# iobrd.net
KiCad netlist of a schematic drawn in Altium Designer
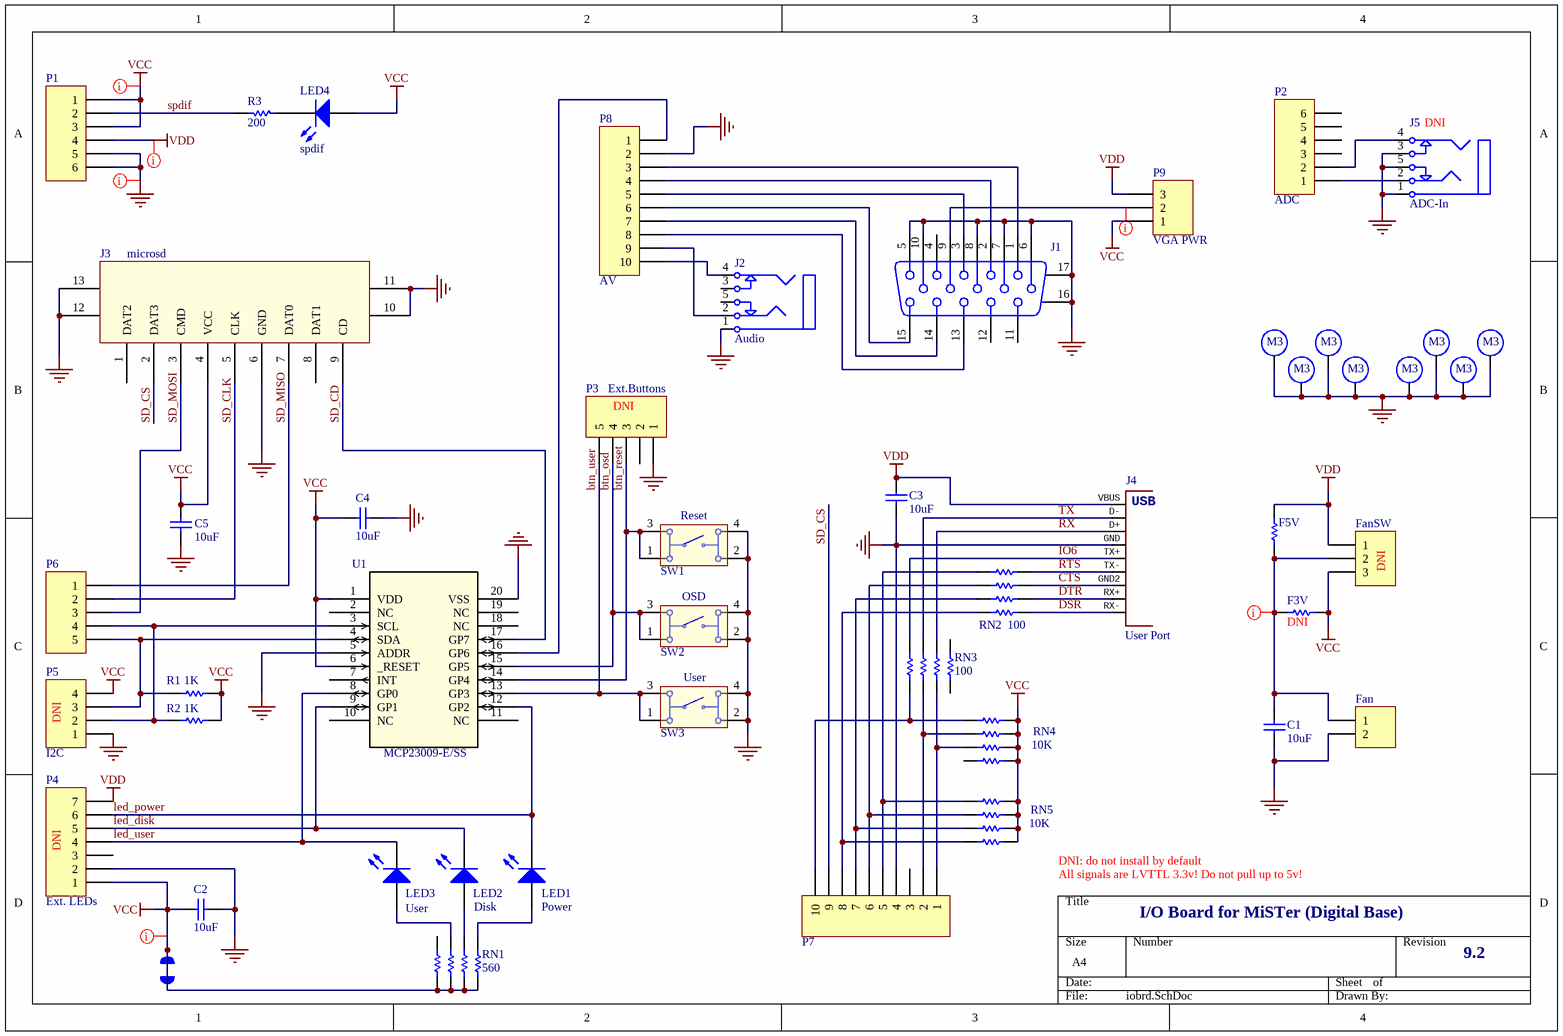
[diagram p0: iobrd.SchDoc]

(export (version "E")
  (design (tool "Eeschema 10.0.6"))
  (components
    (comp (ref "C1")
      (value "10uF")
      (footprint "C0805")
      (description "Ceramic Chip Capacitor - Standard")
      (fields (field (name "Comment") "C0805") (field (name "PUBLISHER") "Altium Limited"))
      (libsource (lib "lib") (part "C0805"))
    )
    (comp (ref "C2")
      (value "10uF")
      (footprint "C0805")
      (description "Ceramic Chip Capacitor - Standard")
      (fields (field (name "Comment") "C0805") (field (name "PUBLISHER") "Altium Limited"))
      (libsource (lib "lib") (part "C0805"))
    )
    (comp (ref "C3")
      (value "10uF")
      (footprint "C0805")
      (description "Ceramic Chip Capacitor - Standard")
      (fields (field (name "Comment") "C0805") (field (name "PUBLISHER") "Altium Limited"))
      (libsource (lib "lib") (part "C0805"))
    )
    (comp (ref "C4")
      (value "10uF")
      (footprint "C0805")
      (description "Ceramic Chip Capacitor - Standard")
      (fields (field (name "Comment") "C0805") (field (name "PUBLISHER") "Altium Limited"))
      (libsource (lib "lib") (part "C0805"))
    )
    (comp (ref "C5")
      (value "10uF")
      (footprint "C0805")
      (description "Ceramic Chip Capacitor - Standard")
      (fields (field (name "Comment") "C0805") (field (name "PUBLISHER") "Altium Limited"))
      (libsource (lib "lib") (part "C0805"))
    )
    (comp (ref "CUT1") (value "CUT") (libsource (lib "lib") (part "CUT")))
    (comp (ref "F3V")
      (value "0")
      (footprint "R0805 - DNI")
      (fields (field (name "PUBLISHER") "Altium Limited"))
      (libsource (lib "lib") (part "R0805"))
    )
    (comp (ref "F5V")
      (value "0")
      (footprint "R0805")
      (fields (field (name "PUBLISHER") "Altium Limited"))
      (libsource (lib "lib") (part "R0805"))
    )
    (comp (ref "Fan")
      (value "Header 2")
      (footprint "HDR1X2")
      (description "Header, 2-Pin")
      (fields (field (name "PUBLISHER") "Altium Limited"))
      (libsource (lib "Miscellaneous Connectors") (part "Header 2"))
    )
    (comp (ref "FanSW")
      (value "Header 3")
      (footprint "HDR1X3")
      (description "Header, 3-Pin")
      (fields (field (name "PUBLISHER") "Altium Limited"))
      (libsource (lib "Miscellaneous Connectors") (part "Header 3"))
    )
    (comp (ref "H1") (value "~") (footprint "M3") (libsource (lib "lib") (part "M3")))
    (comp (ref "H2") (value "~") (footprint "M3") (libsource (lib "lib") (part "M3")))
    (comp (ref "H3") (value "~") (footprint "M3") (libsource (lib "lib") (part "M3")))
    (comp (ref "H4") (value "~") (footprint "M3") (libsource (lib "lib") (part "M3")))
    (comp (ref "H5") (value "~") (footprint "M3") (libsource (lib "lib") (part "M3")))
    (comp (ref "H6") (value "~") (footprint "M3") (libsource (lib "lib") (part "M3")))
    (comp (ref "H7") (value "~") (footprint "M3") (libsource (lib "lib") (part "M3")))
    (comp (ref "H8") (value "~") (footprint "M3") (libsource (lib "lib") (part "M3")))
    (comp (ref "J1") (value "vga") (footprint "VGA") (libsource (lib "lib") (part "vga")))
    (comp (ref "J2") (value "Audio") (footprint "phonejack") (libsource (lib "lib") (part "phonejack")))
    (comp (ref "J3") (value "microsd") (footprint "microsd") (libsource (lib "lib") (part "microsd")))
    (comp (ref "J4")
      (value "User Port")
      (footprint "USB3-A-F-PTH")
      (fields (field (name "USB") "USB"))
      (libsource (lib "lib") (part "USBA30-PTH"))
    )
    (comp (ref "J5")
      (value "ADC-In")
      (footprint "phonejack - DNI")
      (libsource (lib "lib") (part "phonejack"))
    )
    (comp (ref "LED1")
      (value "Power")
      (footprint "LEDR")
      (description "THT LED round mono-color color lens, WL-TMRW, Super Red")
      (fields (field (name "PARTNUMBER") "151031SS04000"))
      (libsource (lib "WL-TMRC THT LED round mono-color color lens") (part "151031SS04000"))
    )
    (comp (ref "LED2")
      (value "Disk")
      (footprint "LEDG")
      (description "THT LED round mono-color color lens, WL-TMRW, Super Red")
      (fields (field (name "PARTNUMBER") "151031SS04000"))
      (libsource (lib "WL-TMRC THT LED round mono-color color lens") (part "151031SS04000"))
    )
    (comp (ref "LED3")
      (value "User")
      (footprint "LEDY")
      (description "THT LED round mono-color color lens, WL-TMRW, Super Red")
      (fields (field (name "PARTNUMBER") "151031SS04000"))
      (libsource (lib "WL-TMRC THT LED round mono-color color lens") (part "151031SS04000"))
    )
    (comp (ref "LED4")
      (value "spdif")
      (footprint "LEDR_angle")
      (description "THT LED round mono-color color lens, WL-TMRW, Super Red")
      (fields (field (name "PARTNUMBER") "151031SS04000"))
      (libsource (lib "WL-TMRC THT LED round mono-color color lens") (part "151031SS04000"))
    )
    (comp (ref "P1")
      (value "~")
      (footprint "HDR1X6")
      (description "Header, 6-Pin")
      (fields (field (name "PUBLISHER") "Altium Limited"))
      (libsource (lib "Miscellaneous Connectors") (part "Header 6"))
    )
    (comp (ref "P2")
      (value "ADC")
      (footprint "HDR1X6")
      (description "Header, 6-Pin")
      (fields (field (name "PUBLISHER") "Altium Limited"))
      (libsource (lib "") (part "Header 6_1"))
    )
    (comp (ref "P3")
      (value "Ext.Buttons")
      (footprint "HDR5")
      (description "Header, 5-Pin")
      (fields (field (name "PUBLISHER") "Altium Limited"))
      (libsource (lib "Miscellaneous Connectors") (part "Header 5"))
    )
    (comp (ref "P4")
      (value "Ext. LEDs")
      (footprint "HDR7")
      (description "Header, 7-Pin")
      (fields (field (name "PUBLISHER") "Altium Limited"))
      (libsource (lib "Miscellaneous Connectors") (part "Header 7"))
    )
    (comp (ref "P5")
      (value "I2C")
      (footprint "HDR1X4")
      (description "Header, 4-Pin")
      (fields (field (name "PUBLISHER") "Altium Limited"))
      (libsource (lib "Miscellaneous Connectors") (part "Header 4"))
    )
    (comp (ref "P6")
      (value "Header 5")
      (footprint "HDR1X5")
      (description "Header, 5-Pin")
      (fields (field (name "PUBLISHER") "Altium Limited"))
      (libsource (lib "") (part "Header 5_1"))
    )
    (comp (ref "P7")
      (value "Header 10")
      (footprint "HDR1X10")
      (description "Header, 10-Pin")
      (fields (field (name "PUBLISHER") "Altium Limited"))
      (libsource (lib "Miscellaneous Connectors") (part "Header 10"))
    )
    (comp (ref "P8")
      (value "AV")
      (footprint "HDR1X10")
      (description "Header, 10-Pin")
      (fields (field (name "PUBLISHER") "Altium Limited"))
      (libsource (lib "Miscellaneous Connectors") (part "Header 10"))
    )
    (comp (ref "P9")
      (value "VGA PWR")
      (footprint "HDR1X3")
      (description "Header, 3-Pin")
      (fields (field (name "PUBLISHER") "Altium Limited"))
      (libsource (lib "") (part "Header 3_1"))
    )
    (comp (ref "R1")
      (value "1K")
      (footprint "R0805")
      (fields (field (name "PUBLISHER") "Altium Limited"))
      (libsource (lib "lib") (part "R0805"))
    )
    (comp (ref "R2")
      (value "1K")
      (footprint "R0805")
      (fields (field (name "PUBLISHER") "Altium Limited"))
      (libsource (lib "lib") (part "R0805"))
    )
    (comp (ref "R3")
      (value "200")
      (footprint "R0805")
      (fields (field (name "PUBLISHER") "Altium Limited"))
      (libsource (lib "lib") (part "R0805"))
    )
    (comp (ref "RN1") (value "560") (footprint "RA1206") (libsource (lib "lib") (part "resistor_set")))
    (comp (ref "RN2") (value "100") (footprint "RA1206") (libsource (lib "lib") (part "resistor_set")))
    (comp (ref "RN3") (value "100") (footprint "RA1206") (libsource (lib "") (part "resistor_set_1")))
    (comp (ref "RN4") (value "10K") (footprint "RA1206") (libsource (lib "lib") (part "resistor_set")))
    (comp (ref "RN5") (value "10K") (footprint "RA1206") (libsource (lib "lib") (part "resistor_set")))
    (comp (ref "SW1")
      (value "Reset")
      (footprint "tact 12x12")
      (libsource (lib "Schlib1") (part "tact 12x12"))
    )
    (comp (ref "SW2") (value "OSD") (footprint "tact 12x12") (libsource (lib "Schlib1") (part "tact 12x12")))
    (comp (ref "SW3") (value "User") (footprint "tact 12x12") (libsource (lib "Schlib1") (part "tact 12x12")))
    (comp (ref "U1")
      (value "MCP23009-E/SS")
      (footprint "SSOP20_MC")
      (description "MCP23009")
      (fields (field (name "COPYRIGHT") "Copyright (C) 2018 Accelerated Designs. All rights reserved"))
      (libsource (lib "lib") (part "MCP23009-E/SS"))
    )
  )
  (nets
    (net (code "1") (name "/CTS") (class "Default")
      (node (ref "J4") (pin "GND2") (pinfunction "GND2_GND2") (pintype "passive"))
      (node (ref "RN2") (pin "5") (pinfunction "5_5") (pintype "passive"))
    )
    (net (code "2") (name "/DSR") (class "Default")
      (node (ref "J4") (pin "RX-") (pinfunction "RX-_RX-") (pintype "passive"))
      (node (ref "RN2") (pin "1") (pinfunction "1_1") (pintype "passive"))
    )
    (net (code "3") (name "/DTR") (class "Default")
      (node (ref "J4") (pin "RX+") (pinfunction "RX+_RX+") (pintype "passive"))
      (node (ref "RN2") (pin "3") (pinfunction "3_3") (pintype "passive"))
    )
    (net (code "4") (name "/IO6") (class "Default")
      (node (ref "J4") (pin "TX+") (pinfunction "TX+_TX+") (pintype "passive"))
      (node (ref "RN3") (pin "1") (pinfunction "1_1") (pintype "passive"))
    )
    (net (code "5") (name "/RTS") (class "Default")
      (node (ref "J4") (pin "TX-") (pinfunction "TX-_TX-") (pintype "passive"))
      (node (ref "RN2") (pin "7") (pinfunction "7_7") (pintype "passive"))
    )
    (net (code "6") (name "/RX") (class "Default")
      (node (ref "J4") (pin "D+") (pinfunction "D+_D+") (pintype "passive"))
      (node (ref "RN3") (pin "5") (pinfunction "5_5") (pintype "passive"))
    )
    (net (code "7") (name "/SD_CD") (class "Default")
      (node (ref "J3") (pin "9") (pinfunction "CD_9") (pintype "passive"))
      (node (ref "U1") (pin "17") (pinfunction "GP7_17") (pintype "passive"))
    )
    (net (code "8") (name "/SD_CLK") (class "Default")
      (node (ref "J3") (pin "5") (pinfunction "CLK_5") (pintype "passive"))
      (node (ref "P6") (pin "2") (pinfunction "2_2") (pintype "passive"))
    )
    (net (code "9") (name "/SD_CS") (class "Default")
      (node (ref "J3") (pin "2") (pinfunction "DAT3_2") (pintype "passive"))
      (node (ref "P7") (pin "9") (pinfunction "9_9") (pintype "passive"))
    )
    (net (code "10") (name "/SD_MISO") (class "Default")
      (node (ref "J3") (pin "7") (pinfunction "DAT0_7") (pintype "passive"))
      (node (ref "P6") (pin "1") (pinfunction "1_1") (pintype "passive"))
    )
    (net (code "11") (name "/SD_MOSI") (class "Default")
      (node (ref "J3") (pin "3") (pinfunction "CMD_3") (pintype "passive"))
      (node (ref "P6") (pin "3") (pinfunction "3_3") (pintype "passive"))
    )
    (net (code "12") (name "/TX") (class "Default")
      (node (ref "J4") (pin "D-") (pinfunction "D-_D-") (pintype "passive"))
      (node (ref "RN3") (pin "3") (pinfunction "3_3") (pintype "passive"))
    )
    (net (code "13") (name "/btn_osd") (class "Default")
      (node (ref "P3") (pin "4") (pinfunction "4_4") (pintype "passive"))
      (node (ref "SW2") (pin "1") (pinfunction "1_1") (pintype "passive"))
      (node (ref "SW2") (pin "3") (pinfunction "3_3") (pintype "passive"))
      (node (ref "U1") (pin "15") (pinfunction "GP5_15") (pintype "passive"))
    )
    (net (code "14") (name "/btn_reset") (class "Default")
      (node (ref "P3") (pin "3") (pinfunction "3_3") (pintype "passive"))
      (node (ref "SW1") (pin "1") (pinfunction "1_1") (pintype "passive"))
      (node (ref "SW1") (pin "3") (pinfunction "3_3") (pintype "passive"))
      (node (ref "U1") (pin "14") (pinfunction "GP4_14") (pintype "passive"))
    )
    (net (code "15") (name "/btn_user") (class "Default")
      (node (ref "P3") (pin "5") (pinfunction "5_5") (pintype "passive"))
      (node (ref "SW3") (pin "1") (pinfunction "1_1") (pintype "passive"))
      (node (ref "SW3") (pin "3") (pinfunction "3_3") (pintype "passive"))
      (node (ref "U1") (pin "13") (pinfunction "GP3_13") (pintype "passive"))
    )
    (net (code "16") (name "/led_disk") (class "Default")
      (node (ref "LED2") (pin "1") (pinfunction "K_1") (pintype "passive"))
      (node (ref "P4") (pin "5") (pinfunction "5_5") (pintype "passive"))
      (node (ref "U1") (pin "9") (pinfunction "GP1_9") (pintype "passive"))
    )
    (net (code "17") (name "/led_power") (class "Default")
      (node (ref "LED1") (pin "1") (pinfunction "K_1") (pintype "passive"))
      (node (ref "P4") (pin "6") (pinfunction "6_6") (pintype "passive"))
      (node (ref "U1") (pin "12") (pinfunction "GP2_12") (pintype "passive"))
    )
    (net (code "18") (name "/led_user") (class "Default")
      (node (ref "LED3") (pin "1") (pinfunction "K_1") (pintype "passive"))
      (node (ref "P4") (pin "4") (pinfunction "4_4") (pintype "passive"))
      (node (ref "U1") (pin "8") (pinfunction "GP0_8") (pintype "passive"))
    )
    (net (code "19") (name "/spdif") (class "Default")
      (node (ref "P1") (pin "2") (pinfunction "2_2") (pintype "passive"))
      (node (ref "R3") (pin "2") (pinfunction "2_2") (pintype "passive"))
    )
    (net (code "20") (name "GND") (class "Default")
      (node (ref "C1") (pin "1") (pinfunction "1_1") (pintype "passive"))
      (node (ref "C2") (pin "1") (pinfunction "1_1") (pintype "passive"))
      (node (ref "C3") (pin "1") (pinfunction "1_1") (pintype "passive"))
      (node (ref "C4") (pin "2") (pinfunction "2_2") (pintype "passive"))
      (node (ref "C5") (pin "1") (pinfunction "1_1") (pintype "passive"))
      (node (ref "Fan") (pin "2") (pinfunction "2_2") (pintype "passive"))
      (node (ref "H1") (pin "1") (pinfunction "1_1") (pintype "passive"))
      (node (ref "H2") (pin "1") (pinfunction "1_1") (pintype "passive"))
      (node (ref "H3") (pin "1") (pinfunction "1_1") (pintype "passive"))
      (node (ref "H4") (pin "1") (pinfunction "1_1") (pintype "passive"))
      (node (ref "H5") (pin "1") (pinfunction "1_1") (pintype "passive"))
      (node (ref "H6") (pin "1") (pinfunction "1_1") (pintype "passive"))
      (node (ref "H7") (pin "1") (pinfunction "1_1") (pintype "passive"))
      (node (ref "H8") (pin "1") (pinfunction "1_1") (pintype "passive"))
      (node (ref "J1") (pin "10") (pinfunction "10_10") (pintype "passive"))
      (node (ref "J1") (pin "16") (pinfunction "MH1_16") (pintype "passive"))
      (node (ref "J1") (pin "17") (pinfunction "MH2_17") (pintype "passive"))
      (node (ref "J1") (pin "5") (pinfunction "5_5") (pintype "passive"))
      (node (ref "J1") (pin "6") (pinfunction "6_6") (pintype "passive"))
      (node (ref "J1") (pin "7") (pinfunction "7_7") (pintype "passive"))
      (node (ref "J1") (pin "8") (pinfunction "8_8") (pintype "passive"))
      (node (ref "J2") (pin "1") (pinfunction "1_1") (pintype "passive"))
      (node (ref "J3") (pin "10") (pinfunction "GND_10") (pintype "passive"))
      (node (ref "J3") (pin "11") (pinfunction "GND_11") (pintype "passive"))
      (node (ref "J3") (pin "12") (pinfunction "GND_12") (pintype "passive"))
      (node (ref "J3") (pin "13") (pinfunction "GND_13") (pintype "passive"))
      (node (ref "J3") (pin "6") (pinfunction "GND_6") (pintype "passive"))
      (node (ref "J4") (pin "GND") (pinfunction "GND_GND") (pintype "passive"))
      (node (ref "J5") (pin "1") (pinfunction "1_1") (pintype "passive"))
      (node (ref "J5") (pin "3") (pinfunction "3_3") (pintype "passive"))
      (node (ref "J5") (pin "5") (pinfunction "5_5") (pintype "passive"))
      (node (ref "P1") (pin "5") (pinfunction "5_5") (pintype "passive"))
      (node (ref "P1") (pin "6") (pinfunction "6_6") (pintype "passive"))
      (node (ref "P3") (pin "1") (pinfunction "1_1") (pintype "passive"))
      (node (ref "P4") (pin "2") (pinfunction "2_2") (pintype "passive"))
      (node (ref "P5") (pin "1") (pinfunction "1_1") (pintype "passive"))
      (node (ref "P7") (pin "4") (pinfunction "4_4") (pintype "passive"))
      (node (ref "P8") (pin "2") (pinfunction "2_2") (pintype "passive"))
      (node (ref "SW1") (pin "2") (pinfunction "2_2") (pintype "passive"))
      (node (ref "SW1") (pin "4") (pinfunction "4_4") (pintype "passive"))
      (node (ref "SW2") (pin "2") (pinfunction "2_2") (pintype "passive"))
      (node (ref "SW2") (pin "4") (pinfunction "4_4") (pintype "passive"))
      (node (ref "SW3") (pin "2") (pinfunction "2_2") (pintype "passive"))
      (node (ref "SW3") (pin "4") (pinfunction "4_4") (pintype "passive"))
      (node (ref "U1") (pin "20") (pinfunction "VSS_20") (pintype "passive"))
      (node (ref "U1") (pin "5") (pinfunction "ADDR_5") (pintype "passive"))
    )
    (net (code "21") (name "Net-(C1-Pad2)") (class "Default")
      (node (ref "C1") (pin "2") (pinfunction "2_2") (pintype "passive"))
      (node (ref "F3V") (pin "2") (pinfunction "2_2") (pintype "passive"))
      (node (ref "F5V") (pin "2") (pinfunction "2_2") (pintype "passive"))
      (node (ref "Fan") (pin "1") (pinfunction "1_1") (pintype "passive"))
      (node (ref "FanSW") (pin "2") (pinfunction "2_2") (pintype "passive"))
    )
    (net (code "22") (name "Net-(J1-Pad1)") (class "Default")
      (node (ref "J1") (pin "1") (pinfunction "1_1") (pintype "passive"))
      (node (ref "P8") (pin "3") (pinfunction "3_3") (pintype "passive"))
    )
    (net (code "23") (name "Net-(J1-Pad2)") (class "Default")
      (node (ref "J1") (pin "2") (pinfunction "2_2") (pintype "passive"))
      (node (ref "P8") (pin "4") (pinfunction "4_4") (pintype "passive"))
    )
    (net (code "24") (name "Net-(J1-Pad3)") (class "Default")
      (node (ref "J1") (pin "3") (pinfunction "3_3") (pintype "passive"))
      (node (ref "P8") (pin "5") (pinfunction "5_5") (pintype "passive"))
    )
    (net (code "25") (name "Net-(J1-Pad9)") (class "Default")
      (node (ref "J1") (pin "9") (pinfunction "9_9") (pintype "passive"))
      (node (ref "P9") (pin "2") (pinfunction "2_2") (pintype "passive"))
    )
    (net (code "26") (name "Net-(J1-Pad13)") (class "Default")
      (node (ref "J1") (pin "13") (pinfunction "13_13") (pintype "passive"))
      (node (ref "P8") (pin "8") (pinfunction "8_8") (pintype "passive"))
    )
    (net (code "27") (name "Net-(J1-Pad14)") (class "Default")
      (node (ref "J1") (pin "14") (pinfunction "14_14") (pintype "passive"))
      (node (ref "P8") (pin "7") (pinfunction "7_7") (pintype "passive"))
    )
    (net (code "28") (name "Net-(J1-Pad15)") (class "Default")
      (node (ref "J1") (pin "15") (pinfunction "15_15") (pintype "passive"))
      (node (ref "P8") (pin "6") (pinfunction "6_6") (pintype "passive"))
    )
    (net (code "29") (name "Net-(J2-Pad2)") (class "Default")
      (node (ref "J2") (pin "2") (pinfunction "2_2") (pintype "passive"))
      (node (ref "P8") (pin "9") (pinfunction "9_9") (pintype "passive"))
    )
    (net (code "30") (name "Net-(J2-Pad4)") (class "Default")
      (node (ref "J2") (pin "4") (pinfunction "4_4") (pintype "passive"))
      (node (ref "P8") (pin "10") (pinfunction "10_10") (pintype "passive"))
    )
    (net (code "31") (name "Net-(J5-Pad2)") (class "Default")
      (node (ref "J5") (pin "2") (pinfunction "2_2") (pintype "passive"))
      (node (ref "P2") (pin "1") (pinfunction "1_1") (pintype "passive"))
    )
    (net (code "32") (name "Net-(J5-Pad4)") (class "Default")
      (node (ref "J5") (pin "4") (pinfunction "4_4") (pintype "passive"))
      (node (ref "P2") (pin "2") (pinfunction "2_2") (pintype "passive"))
    )
    (net (code "33") (name "Net-(LED1-A)") (class "Default")
      (node (ref "LED1") (pin "2") (pinfunction "A_2") (pintype "passive"))
      (node (ref "RN1") (pin "1") (pinfunction "1_1") (pintype "passive"))
    )
    (net (code "34") (name "Net-(LED2-A)") (class "Default")
      (node (ref "LED2") (pin "2") (pinfunction "A_2") (pintype "passive"))
      (node (ref "RN1") (pin "3") (pinfunction "3_3") (pintype "passive"))
    )
    (net (code "35") (name "Net-(LED3-A)") (class "Default")
      (node (ref "LED3") (pin "2") (pinfunction "A_2") (pintype "passive"))
      (node (ref "RN1") (pin "5") (pinfunction "5_5") (pintype "passive"))
    )
    (net (code "36") (name "Net-(LED4-K)") (class "Default")
      (node (ref "LED4") (pin "1") (pinfunction "K_1") (pintype "passive"))
      (node (ref "R3") (pin "1") (pinfunction "1_1") (pintype "passive"))
    )
    (net (code "37") (name "Net-(P7-Pad1)") (class "Default")
      (node (ref "P7") (pin "1") (pinfunction "1_1") (pintype "passive"))
      (node (ref "RN3") (pin "6") (pinfunction "6_6") (pintype "passive"))
      (node (ref "RN4") (pin "5") (pinfunction "5_5") (pintype "passive"))
    )
    (net (code "38") (name "Net-(P7-Pad2)") (class "Default")
      (node (ref "P7") (pin "2") (pinfunction "2_2") (pintype "passive"))
      (node (ref "RN3") (pin "4") (pinfunction "4_4") (pintype "passive"))
      (node (ref "RN4") (pin "3") (pinfunction "3_3") (pintype "passive"))
    )
    (net (code "39") (name "Net-(P7-Pad5)") (class "Default")
      (node (ref "P7") (pin "5") (pinfunction "5_5") (pintype "passive"))
      (node (ref "RN2") (pin "8") (pinfunction "8_8") (pintype "passive"))
      (node (ref "RN5") (pin "8") (pinfunction "8_8") (pintype "passive"))
    )
    (net (code "40") (name "Net-(P7-Pad6)") (class "Default")
      (node (ref "P7") (pin "6") (pinfunction "6_6") (pintype "passive"))
      (node (ref "RN2") (pin "6") (pinfunction "6_6") (pintype "passive"))
      (node (ref "RN5") (pin "6") (pinfunction "6_6") (pintype "passive"))
    )
    (net (code "41") (name "Net-(P7-Pad7)") (class "Default")
      (node (ref "P7") (pin "7") (pinfunction "7_7") (pintype "passive"))
      (node (ref "RN2") (pin "4") (pinfunction "4_4") (pintype "passive"))
      (node (ref "RN5") (pin "4") (pinfunction "4_4") (pintype "passive"))
    )
    (net (code "42") (name "Net-(P7-Pad8)") (class "Default")
      (node (ref "P7") (pin "8") (pinfunction "8_8") (pintype "passive"))
      (node (ref "RN2") (pin "2") (pinfunction "2_2") (pintype "passive"))
      (node (ref "RN5") (pin "2") (pinfunction "2_2") (pintype "passive"))
    )
    (net (code "43") (name "Net-(P7-Pad10)") (class "Default")
      (node (ref "P7") (pin "10") (pinfunction "10_10") (pintype "passive"))
      (node (ref "RN3") (pin "2") (pinfunction "2_2") (pintype "passive"))
      (node (ref "RN4") (pin "1") (pinfunction "1_1") (pintype "passive"))
    )
    (net (code "44") (name "Net-(U1-GP6)") (class "Default")
      (node (ref "P8") (pin "1") (pinfunction "1_1") (pintype "passive"))
      (node (ref "U1") (pin "16") (pinfunction "GP6_16") (pintype "passive"))
    )
    (net (code "45") (name "Net-(U1-SCL)") (class "Default")
      (node (ref "P5") (pin "2") (pinfunction "2_2") (pintype "passive"))
      (node (ref "P6") (pin "4") (pinfunction "4_4") (pintype "passive"))
      (node (ref "R2") (pin "2") (pinfunction "2_2") (pintype "passive"))
      (node (ref "U1") (pin "3") (pinfunction "SCL_3") (pintype "passive"))
    )
    (net (code "46") (name "Net-(U1-SDA)") (class "Default")
      (node (ref "P5") (pin "3") (pinfunction "3_3") (pintype "passive"))
      (node (ref "P6") (pin "5") (pinfunction "5_5") (pintype "passive"))
      (node (ref "R1") (pin "1") (pinfunction "1_1") (pintype "passive"))
      (node (ref "U1") (pin "4") (pinfunction "SDA_4") (pintype "passive"))
    )
    (net (code "47") (name "VCC") (class "Default")
      (node (ref "C2") (pin "2") (pinfunction "2_2") (pintype "passive"))
      (node (ref "C4") (pin "1") (pinfunction "1_1") (pintype "passive"))
      (node (ref "C5") (pin "2") (pinfunction "2_2") (pintype "passive"))
      (node (ref "CUT1") (pin "1") (pinfunction "1_1") (pintype "passive"))
      (node (ref "F3V") (pin "1") (pinfunction "1_1") (pintype "passive"))
      (node (ref "FanSW") (pin "3") (pinfunction "3_3") (pintype "passive"))
      (node (ref "J3") (pin "4") (pinfunction "VCC_4") (pintype "power_in"))
      (node (ref "LED4") (pin "2") (pinfunction "A_2") (pintype "passive"))
      (node (ref "P1") (pin "1") (pinfunction "1_1") (pintype "passive"))
      (node (ref "P1") (pin "3") (pinfunction "3_3") (pintype "passive"))
      (node (ref "P4") (pin "1") (pinfunction "1_1") (pintype "passive"))
      (node (ref "P5") (pin "4") (pinfunction "4_4") (pintype "passive"))
      (node (ref "P9") (pin "1") (pinfunction "1_1") (pintype "passive"))
      (node (ref "R1") (pin "2") (pinfunction "2_2") (pintype "passive"))
      (node (ref "R2") (pin "1") (pinfunction "1_1") (pintype "passive"))
      (node (ref "RN1") (pin "2") (pinfunction "2_2") (pintype "passive"))
      (node (ref "RN1") (pin "4") (pinfunction "4_4") (pintype "passive"))
      (node (ref "RN1") (pin "6") (pinfunction "6_6") (pintype "passive"))
      (node (ref "RN1") (pin "8") (pinfunction "8_8") (pintype "passive"))
      (node (ref "RN4") (pin "2") (pinfunction "2_2") (pintype "passive"))
      (node (ref "RN4") (pin "4") (pinfunction "4_4") (pintype "passive"))
      (node (ref "RN4") (pin "6") (pinfunction "6_6") (pintype "passive"))
      (node (ref "RN4") (pin "8") (pinfunction "8_8") (pintype "passive"))
      (node (ref "RN5") (pin "1") (pinfunction "1_1") (pintype "passive"))
      (node (ref "RN5") (pin "3") (pinfunction "3_3") (pintype "passive"))
      (node (ref "RN5") (pin "5") (pinfunction "5_5") (pintype "passive"))
      (node (ref "RN5") (pin "7") (pinfunction "7_7") (pintype "passive"))
      (node (ref "U1") (pin "1") (pinfunction "VDD_1") (pintype "power_in"))
      (node (ref "U1") (pin "6") (pinfunction "_RESET_6") (pintype "passive"))
    )
    (net (code "48") (name "VDD") (class "Default")
      (node (ref "C3") (pin "2") (pinfunction "2_2") (pintype "passive"))
      (node (ref "F5V") (pin "1") (pinfunction "1_1") (pintype "passive"))
      (node (ref "FanSW") (pin "1") (pinfunction "1_1") (pintype "passive"))
      (node (ref "J4") (pin "VBUS") (pinfunction "VBUS_VBUS") (pintype "passive"))
      (node (ref "P1") (pin "4") (pinfunction "4_4") (pintype "passive"))
      (node (ref "P4") (pin "7") (pinfunction "7_7") (pintype "passive"))
      (node (ref "P9") (pin "3") (pinfunction "3_3") (pintype "passive"))
    )
    (net (code "49") (name "unconnected-(J1-Pad4)") (class "Default")
      (node (ref "J1") (pin "4") (pinfunction "4_4") (pintype "passive"))
    )
    (net (code "50") (name "unconnected-(J1-Pad11)") (class "Default")
      (node (ref "J1") (pin "11") (pinfunction "11_11") (pintype "passive"))
    )
    (net (code "51") (name "unconnected-(J1-Pad12)") (class "Default")
      (node (ref "J1") (pin "12") (pinfunction "12_12") (pintype "passive"))
    )
    (net (code "52") (name "unconnected-(J2-Pad3)") (class "Default")
      (node (ref "J2") (pin "3") (pinfunction "3_3") (pintype "passive"))
    )
    (net (code "53") (name "unconnected-(J2-Pad5)") (class "Default")
      (node (ref "J2") (pin "5") (pinfunction "5_5") (pintype "passive"))
    )
    (net (code "54") (name "unconnected-(J3-DAT1-Pad8)") (class "Default")
      (node (ref "J3") (pin "8") (pinfunction "DAT1_8") (pintype "passive"))
    )
    (net (code "55") (name "unconnected-(J3-DAT2-Pad1)") (class "Default")
      (node (ref "J3") (pin "1") (pinfunction "DAT2_1") (pintype "passive"))
    )
    (net (code "56") (name "unconnected-(P2-Pad3)") (class "Default")
      (node (ref "P2") (pin "3") (pinfunction "3_3") (pintype "passive"))
    )
    (net (code "57") (name "unconnected-(P2-Pad4)") (class "Default")
      (node (ref "P2") (pin "4") (pinfunction "4_4") (pintype "passive"))
    )
    (net (code "58") (name "unconnected-(P2-Pad5)") (class "Default")
      (node (ref "P2") (pin "5") (pinfunction "5_5") (pintype "passive"))
    )
    (net (code "59") (name "unconnected-(P2-Pad6)") (class "Default")
      (node (ref "P2") (pin "6") (pinfunction "6_6") (pintype "passive"))
    )
    (net (code "60") (name "unconnected-(P3-Pad2)") (class "Default")
      (node (ref "P3") (pin "2") (pinfunction "2_2") (pintype "passive"))
    )
    (net (code "61") (name "unconnected-(P4-Pad3)") (class "Default")
      (node (ref "P4") (pin "3") (pinfunction "3_3") (pintype "passive"))
    )
    (net (code "62") (name "unconnected-(P7-Pad3)") (class "Default")
      (node (ref "P7") (pin "3") (pinfunction "3_3") (pintype "passive"))
    )
    (net (code "63") (name "unconnected-(RN1-Pad7)") (class "Default")
      (node (ref "RN1") (pin "7") (pinfunction "7_7") (pintype "passive"))
    )
    (net (code "64") (name "unconnected-(RN3-Pad7)") (class "Default")
      (node (ref "RN3") (pin "7") (pinfunction "7_7") (pintype "passive"))
    )
    (net (code "65") (name "unconnected-(RN3-Pad8)") (class "Default")
      (node (ref "RN3") (pin "8") (pinfunction "8_8") (pintype "passive"))
    )
    (net (code "66") (name "unconnected-(RN4-Pad7)") (class "Default")
      (node (ref "RN4") (pin "7") (pinfunction "7_7") (pintype "passive"))
    )
    (net (code "67") (name "unconnected-(U1-INT-Pad7)") (class "Default")
      (node (ref "U1") (pin "7") (pinfunction "INT_7") (pintype "passive"))
    )
    (net (code "68") (name "unconnected-(U1-NC-Pad2)") (class "Default")
      (node (ref "U1") (pin "2") (pinfunction "NC_2") (pintype "passive"))
    )
    (net (code "69") (name "unconnected-(U1-NC-Pad10)") (class "Default")
      (node (ref "U1") (pin "10") (pinfunction "NC_10") (pintype "passive"))
    )
    (net (code "70") (name "unconnected-(U1-NC-Pad11)") (class "Default")
      (node (ref "U1") (pin "11") (pinfunction "NC_11") (pintype "passive"))
    )
    (net (code "71") (name "unconnected-(U1-NC-Pad18)") (class "Default")
      (node (ref "U1") (pin "18") (pinfunction "NC_18") (pintype "passive"))
    )
    (net (code "72") (name "unconnected-(U1-NC-Pad19)") (class "Default")
      (node (ref "U1") (pin "19") (pinfunction "NC_19") (pintype "passive"))
    )
  )
)
